# 02-MCU.net
KiCad netlist of a schematic drawn in Altium Designer
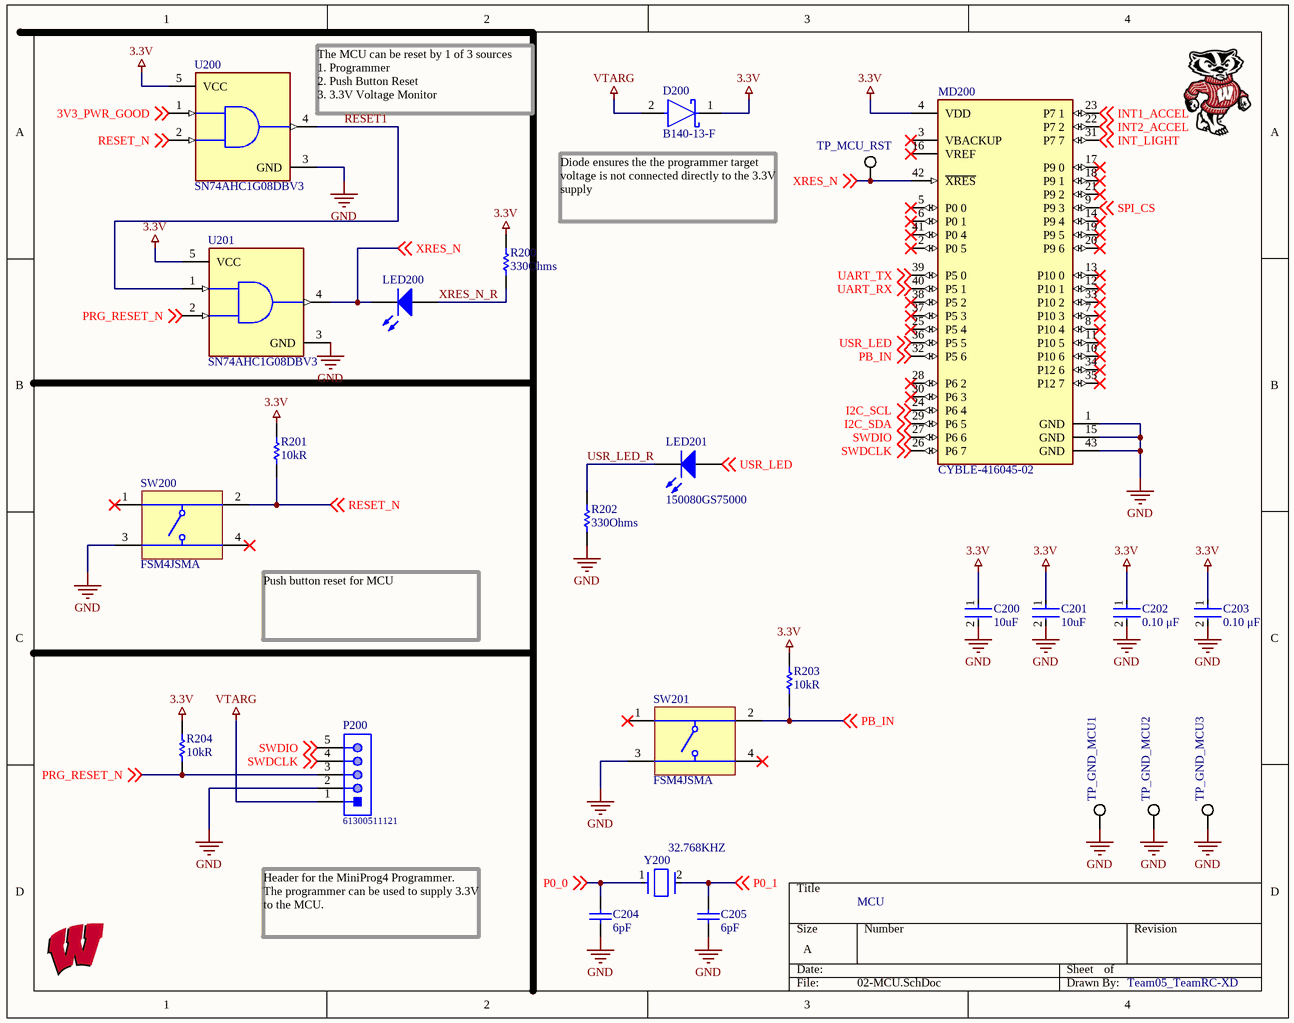
[diagram p0: 02-MCU.SchDoc]

(export (version "E")
  (design (tool "Eeschema 10.0.6"))
  (components
    (comp (ref "C200")
      (value "10uF")
      (footprint "FP-C0805C-DG-MFG")
      (description "CAP CER 10UF 10V X5R 0805")
      (fields (field (name "TOLERANCE") "10%") (field (name "MANUFACTURER PART NUMBER") "C0805C106K8PACTU"))
      (libsource (lib "Altium Content Vault") (part "11868f565c42a9108669ba33697ecf6"))
    )
    (comp (ref "C201")
      (value "10uF")
      (footprint "FP-C0805C-DG-MFG")
      (description "CAP CER 10UF 10V X5R 0805")
      (fields (field (name "TOLERANCE") "10%") (field (name "MANUFACTURER PART NUMBER") "C0805C106K8PACTU"))
      (libsource (lib "Altium Content Vault") (part "11868f565c42a9108669ba33697ecf6"))
    )
    (comp (ref "C202")
      (value "0.10 μF")
      (footprint "FP-C0805C-DN-MFG")
      (description "CAP CER 0.1UF 50V X7R 0805")
      (fields
        (field (name "MANUFACTURER PART NUMBER") "C0805C104K5RACTU")
        (field (name "MANUFACTURER") "KEMET")
      )
      (libsource (lib "Altium Content Vault") (part "b4654b650e69147ec39a6b967a45e02"))
    )
    (comp (ref "C203")
      (value "0.10 μF")
      (footprint "FP-C0805C-DN-MFG")
      (description "CAP CER 0.1UF 50V X7R 0805")
      (fields
        (field (name "MANUFACTURER PART NUMBER") "C0805C104K5RACTU")
        (field (name "MANUFACTURER") "KEMET")
      )
      (libsource (lib "Altium Content Vault") (part "b4654b650e69147ec39a6b967a45e02"))
    )
    (comp (ref "C204")
      (value "08055A6R0CAT2A")
      (footprint "CAPC2013X94X50LL20T25")
      (description "CAP CER 6PF 50V")
      (fields (field (name "MANUFACTURER") "AVX Interconnect / Elco") (field (name "CAPACITANCE") "6pF"))
      (libsource (lib "Altium Content Vault") (part "CAP"))
    )
    (comp (ref "C205")
      (value "08055A6R0CAT2A")
      (footprint "CAPC2013X94X50LL20T25")
      (description "CAP CER 6PF 50V")
      (fields (field (name "MANUFACTURER") "AVX Interconnect / Elco") (field (name "CAPACITANCE") "6pF"))
      (libsource (lib "Altium Content Vault") (part "CAP"))
    )
    (comp (ref "D200")
      (value "B140-13-F")
      (footprint "FP-SMA-MFG")
      (description "DIODE SCHOTTKY 40V 1A SMA")
      (libsource (lib "Altium Content Vault") (part "1d6ec82d83fb6aee721767c19dac4b9"))
    )
    (comp (ref "LED200")
      (value "150080RS75000")
      (footprint "0805_A")
      (description "SMD mono-color Chip LED, WL-SMCW, Red")
      (fields (field (name "MANUFACTURER") "Wuerth Elektronik"))
      (libsource (lib "Altium Content Vault") (part "WE-LED_K1A2-2"))
    )
    (comp (ref "LED201")
      (value "150080GS75000")
      (footprint "0805_A")
      (description "SMD mono-color Chip LED, WL-SMCW, Green")
      (fields (field (name "MANUFACTURER") "Wuerth Elektronik"))
      (libsource (lib "Altium Content Vault") (part "WE-LED_K1A2-2"))
    )
    (comp (ref "MD200")
      (value "CYBLE-416045-02")
      (footprint "FP-CYBLE-416045-02-MFG")
      (description "RF TXRX MOD BLUETOOTH TRACE ANT")
      (fields
        (field (name "OCTOPART") "https://octopart.com/cyble-416045-02-cypress+semiconductor-96386825")
        (field (name "MANUFACTURER") "Cypress Semiconductor")
      )
      (libsource (lib "Altium Content Vault") (part "10a29a4e77099fbb6f911efb04878b1"))
    )
    (comp (ref "P200")
      (value "61300511121")
      (footprint "61300511121")
      (description "THT Vertical Pin Header WR-PHD, Pitch 2.54 mm, Single Row, 5 pins")
      (fields (field (name "MANUFACTURER") "Wurth Elektronik") (field (name "PUBLISHER") "WurthElektronik"))
      (libsource (lib "Altium Content Vault") (part "WE-CN-1P-M-R5"))
    )
    (comp (ref "R200")
      (value "RC0805FR-07330RL")
      (footprint "RESC2013X60X35LL10T20")
      (description "Chip Resistor, 330 Ohm, +/- 1%, 125 mW, -55 to 155 degC, 0805 (2012 Metric), RoHS, Tape and Reel")
      (fields
        (field (name "MANUFACTURER") "Yageo")
        (field (name "TOLERANCE") "1%")
        (field (name "RESISTANCE") "330Ohms")
      )
      (libsource (lib "Altium Content Vault") (part "RES-2"))
    )
    (comp (ref "R201")
      (value "RC0805FR-0710KL")
      (footprint "RESC2013X60X35NL10T20")
      (description "Chip Resistor, 10 KOhm, +/- 1%, 0.125 W, -55 to 155 degC, 0805 (2012 Metric), RoHS, Tape and Reel")
      (fields
        (field (name "MANUFACTURER") "Yageo")
        (field (name "RESISTANCE") "10kR")
        (field (name "TOLERANCE") "1%")
      )
      (libsource (lib "Altium Content Vault") (part "RES-2"))
    )
    (comp (ref "R202")
      (value "RC0805FR-07330RL")
      (footprint "RESC2013X60X35LL10T20")
      (description "Chip Resistor, 330 Ohm, +/- 1%, 125 mW, -55 to 155 degC, 0805 (2012 Metric), RoHS, Tape and Reel")
      (fields
        (field (name "MANUFACTURER") "Yageo")
        (field (name "TOLERANCE") "1%")
        (field (name "RESISTANCE") "330Ohms")
      )
      (libsource (lib "Altium Content Vault") (part "RES-2"))
    )
    (comp (ref "R203")
      (value "RC0805FR-0710KL")
      (footprint "RESC2013X60X35NL10T20")
      (description "Chip Resistor, 10 KOhm, +/- 1%, 0.125 W, -55 to 155 degC, 0805 (2012 Metric), RoHS, Tape and Reel")
      (fields
        (field (name "MANUFACTURER") "Yageo")
        (field (name "RESISTANCE") "10kR")
        (field (name "TOLERANCE") "1%")
      )
      (libsource (lib "Altium Content Vault") (part "RES-2"))
    )
    (comp (ref "R204")
      (value "RC0805FR-0710KL")
      (footprint "RESC2013X60X35NL10T20")
      (description "Chip Resistor, 10 KOhm, +/- 1%, 0.125 W, -55 to 155 degC, 0805 (2012 Metric), RoHS, Tape and Reel")
      (fields
        (field (name "MANUFACTURER") "Yageo")
        (field (name "RESISTANCE") "10kR")
        (field (name "TOLERANCE") "1%")
      )
      (libsource (lib "Altium Content Vault") (part "RES-2"))
    )
    (comp (ref "SW200")
      (value "FSM4JSMA")
      (footprint "TECO-FSM4JSMA_V")
      (description "Swicth, SPST, 24 V, -35 to 85 degC, 4-Pin SMD, RoHS, Tape and Reel")
      (fields (field (name "MANUFACTURER") "TE Connectivity"))
      (libsource (lib "Altium Content Vault") (part "SW-SPST-4_A"))
    )
    (comp (ref "SW201")
      (value "FSM4JSMA")
      (footprint "TECO-FSM4JSMA_V")
      (description "Swicth, SPST, 24 V, -35 to 85 degC, 4-Pin SMD, RoHS, Tape and Reel")
      (fields (field (name "MANUFACTURER") "TE Connectivity"))
      (libsource (lib "Altium Content Vault") (part "SW-SPST-4_A"))
    )
    (comp (ref "TP_GND_MCU1")
      (value "5019")
      (footprint "KSTN-5019_V")
      (description "Test Point, 1 Position SMD, RoHS, Tape and Reel")
      (libsource (lib "Altium Content Vault") (part "TESTPOINT_WHITE"))
    )
    (comp (ref "TP_GND_MCU2")
      (value "5019")
      (footprint "KSTN-5019_V")
      (description "Test Point, 1 Position SMD, RoHS, Tape and Reel")
      (libsource (lib "Altium Content Vault") (part "TESTPOINT_WHITE"))
    )
    (comp (ref "TP_GND_MCU3")
      (value "5019")
      (footprint "KSTN-5019_V")
      (description "Test Point, 1 Position SMD, RoHS, Tape and Reel")
      (libsource (lib "Altium Content Vault") (part "TESTPOINT_WHITE"))
    )
    (comp (ref "TP_MCU_RST")
      (value "5019")
      (footprint "KSTN-5019_V")
      (description "Test Point, 1 Position SMD, RoHS, Tape and Reel")
      (libsource (lib "Altium Content Vault") (part "TESTPOINT_WHITE"))
    )
    (comp (ref "U200")
      (value "SN74AHC1G08DBV3")
      (footprint "FP-DBV0005A-IPC_C")
      (description "IC GATE AND 1CH 2-INP SOT23-5")
      (libsource (lib "Altium Content Vault") (part "675e79b427d6219a5295bf943425e1c"))
    )
    (comp (ref "U201")
      (value "SN74AHC1G08DBV3")
      (footprint "FP-DBV0005A-IPC_C")
      (description "IC GATE AND 1CH 2-INP SOT23-5")
      (libsource (lib "Altium Content Vault") (part "675e79b427d6219a5295bf943425e1c"))
    )
    (comp (ref "Y200")
      (value "32.768KHZ")
      (footprint "FP-ABS07-120-MFG")
      (description "CRYSTAL 32.7680KHZ 6PF SMD")
      (fields (field (name "TOLERANCE") "20ppm"))
      (libsource (lib "Altium Content Vault") (part "c23a69dc6c9e2f18f2079038eb95dd1"))
    )
  )
  (nets
    (net (code "1") (name "/RESET1") (class "Default")
      (node (ref "U200") (pin "4") (pinfunction "Y_4") (pintype "output"))
      (node (ref "U201") (pin "1") (pinfunction "A_1") (pintype "input"))
    )
    (net (code "2") (name "/USR_LED_R") (class "Default")
      (node (ref "LED201") (pin "1") (pinfunction "K_1") (pintype "passive"))
      (node (ref "R202") (pin "2") (pinfunction "2_2") (pintype "passive"))
    )
    (net (code "3") (name "/XRES_N_R") (class "Default")
      (node (ref "LED200") (pin "2") (pinfunction "A_2") (pintype "passive"))
      (node (ref "R200") (pin "1") (pinfunction "1_1") (pintype "passive"))
    )
    (net (code "4") (name "3.3V") (class "Default")
      (node (ref "C200") (pin "1") (pinfunction "1_1") (pintype "passive"))
      (node (ref "C201") (pin "1") (pinfunction "1_1") (pintype "passive"))
      (node (ref "C202") (pin "1") (pinfunction "1_1") (pintype "passive"))
      (node (ref "C203") (pin "1") (pinfunction "1_1") (pintype "passive"))
      (node (ref "D200") (pin "1") (pinfunction "C_1") (pintype "passive"))
      (node (ref "MD200") (pin "4") (pinfunction "VDD_4") (pintype "power_in"))
      (node (ref "R200") (pin "2") (pinfunction "2_2") (pintype "passive"))
      (node (ref "R201") (pin "2") (pinfunction "2_2") (pintype "passive"))
      (node (ref "R203") (pin "2") (pinfunction "2_2") (pintype "passive"))
      (node (ref "R204") (pin "2") (pinfunction "2_2") (pintype "passive"))
      (node (ref "U200") (pin "5") (pinfunction "VCC_5") (pintype "power_in"))
      (node (ref "U201") (pin "5") (pinfunction "VCC_5") (pintype "power_in"))
    )
    (net (code "5") (name "3V3_PWR_GOOD") (class "Default")
      (node (ref "U200") (pin "1") (pinfunction "A_1") (pintype "input"))
    )
    (net (code "6") (name "GND") (class "Default")
      (node (ref "C200") (pin "2") (pinfunction "2_2") (pintype "passive"))
      (node (ref "C201") (pin "2") (pinfunction "2_2") (pintype "passive"))
      (node (ref "C202") (pin "2") (pinfunction "2_2") (pintype "passive"))
      (node (ref "C203") (pin "2") (pinfunction "2_2") (pintype "passive"))
      (node (ref "C204") (pin "1") (pinfunction "1_1") (pintype "passive"))
      (node (ref "C205") (pin "1") (pinfunction "1_1") (pintype "passive"))
      (node (ref "MD200") (pin "1") (pinfunction "GND_1") (pintype "power_in"))
      (node (ref "MD200") (pin "15") (pinfunction "GND_15") (pintype "power_in"))
      (node (ref "MD200") (pin "43") (pinfunction "GND_43") (pintype "power_in"))
      (node (ref "P200") (pin "2") (pinfunction "2_2") (pintype "passive"))
      (node (ref "R202") (pin "1") (pinfunction "1_1") (pintype "passive"))
      (node (ref "SW200") (pin "3") (pinfunction "3_3") (pintype "passive"))
      (node (ref "SW201") (pin "3") (pinfunction "3_3") (pintype "passive"))
      (node (ref "TP_GND_MCU1") (pin "1") (pinfunction "1_1") (pintype "passive"))
      (node (ref "TP_GND_MCU2") (pin "1") (pinfunction "1_1") (pintype "passive"))
      (node (ref "TP_GND_MCU3") (pin "1") (pinfunction "1_1") (pintype "passive"))
      (node (ref "U200") (pin "3") (pinfunction "GND_3") (pintype "power_in"))
      (node (ref "U201") (pin "3") (pinfunction "GND_3") (pintype "power_in"))
    )
    (net (code "7") (name "I2C_SCL") (class "Default")
      (node (ref "MD200") (pin "24") (pinfunction "P6_4_24") (pintype "bidirectional"))
    )
    (net (code "8") (name "I2C_SDA") (class "Default")
      (node (ref "MD200") (pin "29") (pinfunction "P6_5_29") (pintype "bidirectional"))
    )
    (net (code "9") (name "INT1_ACCEL") (class "Default")
      (node (ref "MD200") (pin "23") (pinfunction "P7_1_23") (pintype "bidirectional"))
    )
    (net (code "10") (name "INT2_ACCEL") (class "Default")
      (node (ref "MD200") (pin "22") (pinfunction "P7_2_22") (pintype "bidirectional"))
    )
    (net (code "11") (name "INT_LIGHT") (class "Default")
      (node (ref "MD200") (pin "31") (pinfunction "P7_7_31") (pintype "bidirectional"))
    )
    (net (code "12") (name "P0_0") (class "Default")
      (node (ref "C204") (pin "2") (pinfunction "2_2") (pintype "passive"))
      (node (ref "Y200") (pin "1") (pinfunction "1_1") (pintype "passive"))
    )
    (net (code "13") (name "P0_1") (class "Default")
      (node (ref "C205") (pin "2") (pinfunction "2_2") (pintype "passive"))
      (node (ref "Y200") (pin "2") (pinfunction "2_2") (pintype "passive"))
    )
    (net (code "14") (name "PB_IN") (class "Default")
      (node (ref "MD200") (pin "32") (pinfunction "P5_6_32") (pintype "bidirectional"))
      (node (ref "R203") (pin "1") (pinfunction "1_1") (pintype "passive"))
      (node (ref "SW201") (pin "2") (pinfunction "2_2") (pintype "passive"))
    )
    (net (code "15") (name "PRG_RESET_N") (class "Default")
      (node (ref "P200") (pin "3") (pinfunction "3_3") (pintype "passive"))
      (node (ref "R204") (pin "1") (pinfunction "1_1") (pintype "passive"))
      (node (ref "U201") (pin "2") (pinfunction "B_2") (pintype "input"))
    )
    (net (code "16") (name "RESET_N") (class "Default")
      (node (ref "R201") (pin "1") (pinfunction "1_1") (pintype "passive"))
      (node (ref "SW200") (pin "2") (pinfunction "2_2") (pintype "passive"))
      (node (ref "U200") (pin "2") (pinfunction "B_2") (pintype "input"))
    )
    (net (code "17") (name "SPI_CS") (class "Default")
      (node (ref "MD200") (pin "9") (pinfunction "P9_3_9") (pintype "bidirectional"))
    )
    (net (code "18") (name "SWDCLK") (class "Default")
      (node (ref "MD200") (pin "26") (pinfunction "P6_7_26") (pintype "bidirectional"))
      (node (ref "P200") (pin "4") (pinfunction "4_4") (pintype "passive"))
    )
    (net (code "19") (name "SWDIO") (class "Default")
      (node (ref "MD200") (pin "27") (pinfunction "P6_6_27") (pintype "bidirectional"))
      (node (ref "P200") (pin "5") (pinfunction "5_5") (pintype "passive"))
    )
    (net (code "20") (name "UART_RX") (class "Default")
      (node (ref "MD200") (pin "40") (pinfunction "P5_1_40") (pintype "bidirectional"))
    )
    (net (code "21") (name "UART_TX") (class "Default")
      (node (ref "MD200") (pin "39") (pinfunction "P5_0_39") (pintype "bidirectional"))
    )
    (net (code "22") (name "USR_LED") (class "Default")
      (node (ref "LED201") (pin "2") (pinfunction "A_2") (pintype "passive"))
      (node (ref "MD200") (pin "36") (pinfunction "P5_5_36") (pintype "bidirectional"))
    )
    (net (code "23") (name "VTARG") (class "Default")
      (node (ref "D200") (pin "2") (pinfunction "A_2") (pintype "passive"))
      (node (ref "P200") (pin "1") (pinfunction "1_1") (pintype "passive"))
    )
    (net (code "24") (name "XRES_N") (class "Default")
      (node (ref "LED200") (pin "1") (pinfunction "K_1") (pintype "passive"))
      (node (ref "MD200") (pin "42") (pinfunction "~{XRES}_42") (pintype "input"))
      (node (ref "TP_MCU_RST") (pin "1") (pinfunction "1_1") (pintype "passive"))
      (node (ref "U201") (pin "4") (pinfunction "Y_4") (pintype "output"))
    )
    (net (code "25") (name "unconnected-(MD200-P0_0-Pad5)") (class "Default")
      (node (ref "MD200") (pin "5") (pinfunction "P0_0_5") (pintype "bidirectional+no_connect"))
    )
    (net (code "26") (name "unconnected-(MD200-P0_1-Pad6)") (class "Default")
      (node (ref "MD200") (pin "6") (pinfunction "P0_1_6") (pintype "bidirectional+no_connect"))
    )
    (net (code "27") (name "unconnected-(MD200-P0_4-Pad41)") (class "Default")
      (node (ref "MD200") (pin "41") (pinfunction "P0_4_41") (pintype "bidirectional+no_connect"))
    )
    (net (code "28") (name "unconnected-(MD200-P0_5-Pad2)") (class "Default")
      (node (ref "MD200") (pin "2") (pinfunction "P0_5_2") (pintype "bidirectional+no_connect"))
    )
    (net (code "29") (name "unconnected-(MD200-P5_2-Pad38)") (class "Default")
      (node (ref "MD200") (pin "38") (pinfunction "P5_2_38") (pintype "bidirectional+no_connect"))
    )
    (net (code "30") (name "unconnected-(MD200-P5_3-Pad37)") (class "Default")
      (node (ref "MD200") (pin "37") (pinfunction "P5_3_37") (pintype "bidirectional+no_connect"))
    )
    (net (code "31") (name "unconnected-(MD200-P5_4-Pad25)") (class "Default")
      (node (ref "MD200") (pin "25") (pinfunction "P5_4_25") (pintype "bidirectional+no_connect"))
    )
    (net (code "32") (name "unconnected-(MD200-P6_2-Pad28)") (class "Default")
      (node (ref "MD200") (pin "28") (pinfunction "P6_2_28") (pintype "bidirectional+no_connect"))
    )
    (net (code "33") (name "unconnected-(MD200-P6_3-Pad30)") (class "Default")
      (node (ref "MD200") (pin "30") (pinfunction "P6_3_30") (pintype "bidirectional+no_connect"))
    )
    (net (code "34") (name "unconnected-(MD200-P9_0-Pad17)") (class "Default")
      (node (ref "MD200") (pin "17") (pinfunction "P9_0_17") (pintype "bidirectional+no_connect"))
    )
    (net (code "35") (name "unconnected-(MD200-P9_1-Pad18)") (class "Default")
      (node (ref "MD200") (pin "18") (pinfunction "P9_1_18") (pintype "bidirectional+no_connect"))
    )
    (net (code "36") (name "unconnected-(MD200-P9_2-Pad21)") (class "Default")
      (node (ref "MD200") (pin "21") (pinfunction "P9_2_21") (pintype "bidirectional+no_connect"))
    )
    (net (code "37") (name "unconnected-(MD200-P9_4-Pad14)") (class "Default")
      (node (ref "MD200") (pin "14") (pinfunction "P9_4_14") (pintype "bidirectional+no_connect"))
    )
    (net (code "38") (name "unconnected-(MD200-P9_5-Pad19)") (class "Default")
      (node (ref "MD200") (pin "19") (pinfunction "P9_5_19") (pintype "bidirectional+no_connect"))
    )
    (net (code "39") (name "unconnected-(MD200-P9_6-Pad20)") (class "Default")
      (node (ref "MD200") (pin "20") (pinfunction "P9_6_20") (pintype "bidirectional+no_connect"))
    )
    (net (code "40") (name "unconnected-(MD200-P10_0-Pad13)") (class "Default")
      (node (ref "MD200") (pin "13") (pinfunction "P10_0_13") (pintype "bidirectional+no_connect"))
    )
    (net (code "41") (name "unconnected-(MD200-P10_1-Pad12)") (class "Default")
      (node (ref "MD200") (pin "12") (pinfunction "P10_1_12") (pintype "bidirectional+no_connect"))
    )
    (net (code "42") (name "unconnected-(MD200-P10_2-Pad33)") (class "Default")
      (node (ref "MD200") (pin "33") (pinfunction "P10_2_33") (pintype "bidirectional+no_connect"))
    )
    (net (code "43") (name "unconnected-(MD200-P10_3-Pad7)") (class "Default")
      (node (ref "MD200") (pin "7") (pinfunction "P10_3_7") (pintype "bidirectional+no_connect"))
    )
    (net (code "44") (name "unconnected-(MD200-P10_4-Pad8)") (class "Default")
      (node (ref "MD200") (pin "8") (pinfunction "P10_4_8") (pintype "bidirectional+no_connect"))
    )
    (net (code "45") (name "unconnected-(MD200-P10_5-Pad11)") (class "Default")
      (node (ref "MD200") (pin "11") (pinfunction "P10_5_11") (pintype "bidirectional+no_connect"))
    )
    (net (code "46") (name "unconnected-(MD200-P10_6-Pad10)") (class "Default")
      (node (ref "MD200") (pin "10") (pinfunction "P10_6_10") (pintype "bidirectional+no_connect"))
    )
    (net (code "47") (name "unconnected-(MD200-P12_6-Pad34)") (class "Default")
      (node (ref "MD200") (pin "34") (pinfunction "P12_6_34") (pintype "bidirectional+no_connect"))
    )
    (net (code "48") (name "unconnected-(MD200-P12_7-Pad35)") (class "Default")
      (node (ref "MD200") (pin "35") (pinfunction "P12_7_35") (pintype "bidirectional+no_connect"))
    )
    (net (code "49") (name "unconnected-(MD200-VBACKUP-Pad3)") (class "Default")
      (node (ref "MD200") (pin "3") (pinfunction "VBACKUP_3") (pintype "power_in+no_connect"))
    )
    (net (code "50") (name "unconnected-(MD200-VREF-Pad16)") (class "Default")
      (node (ref "MD200") (pin "16") (pinfunction "VREF_16") (pintype "power_in+no_connect"))
    )
    (net (code "51") (name "unconnected-(SW200-Pad1)") (class "Default")
      (node (ref "SW200") (pin "1") (pinfunction "1_1") (pintype "passive+no_connect"))
    )
    (net (code "52") (name "unconnected-(SW200-Pad4)") (class "Default")
      (node (ref "SW200") (pin "4") (pinfunction "4_4") (pintype "passive+no_connect"))
    )
    (net (code "53") (name "unconnected-(SW201-Pad1)") (class "Default")
      (node (ref "SW201") (pin "1") (pinfunction "1_1") (pintype "passive+no_connect"))
    )
    (net (code "54") (name "unconnected-(SW201-Pad4)") (class "Default")
      (node (ref "SW201") (pin "4") (pinfunction "4_4") (pintype "passive+no_connect"))
    )
  )
)
